# RH_Light_House.net
KiCad netlist of a schematic drawn in EasyEDA Pro
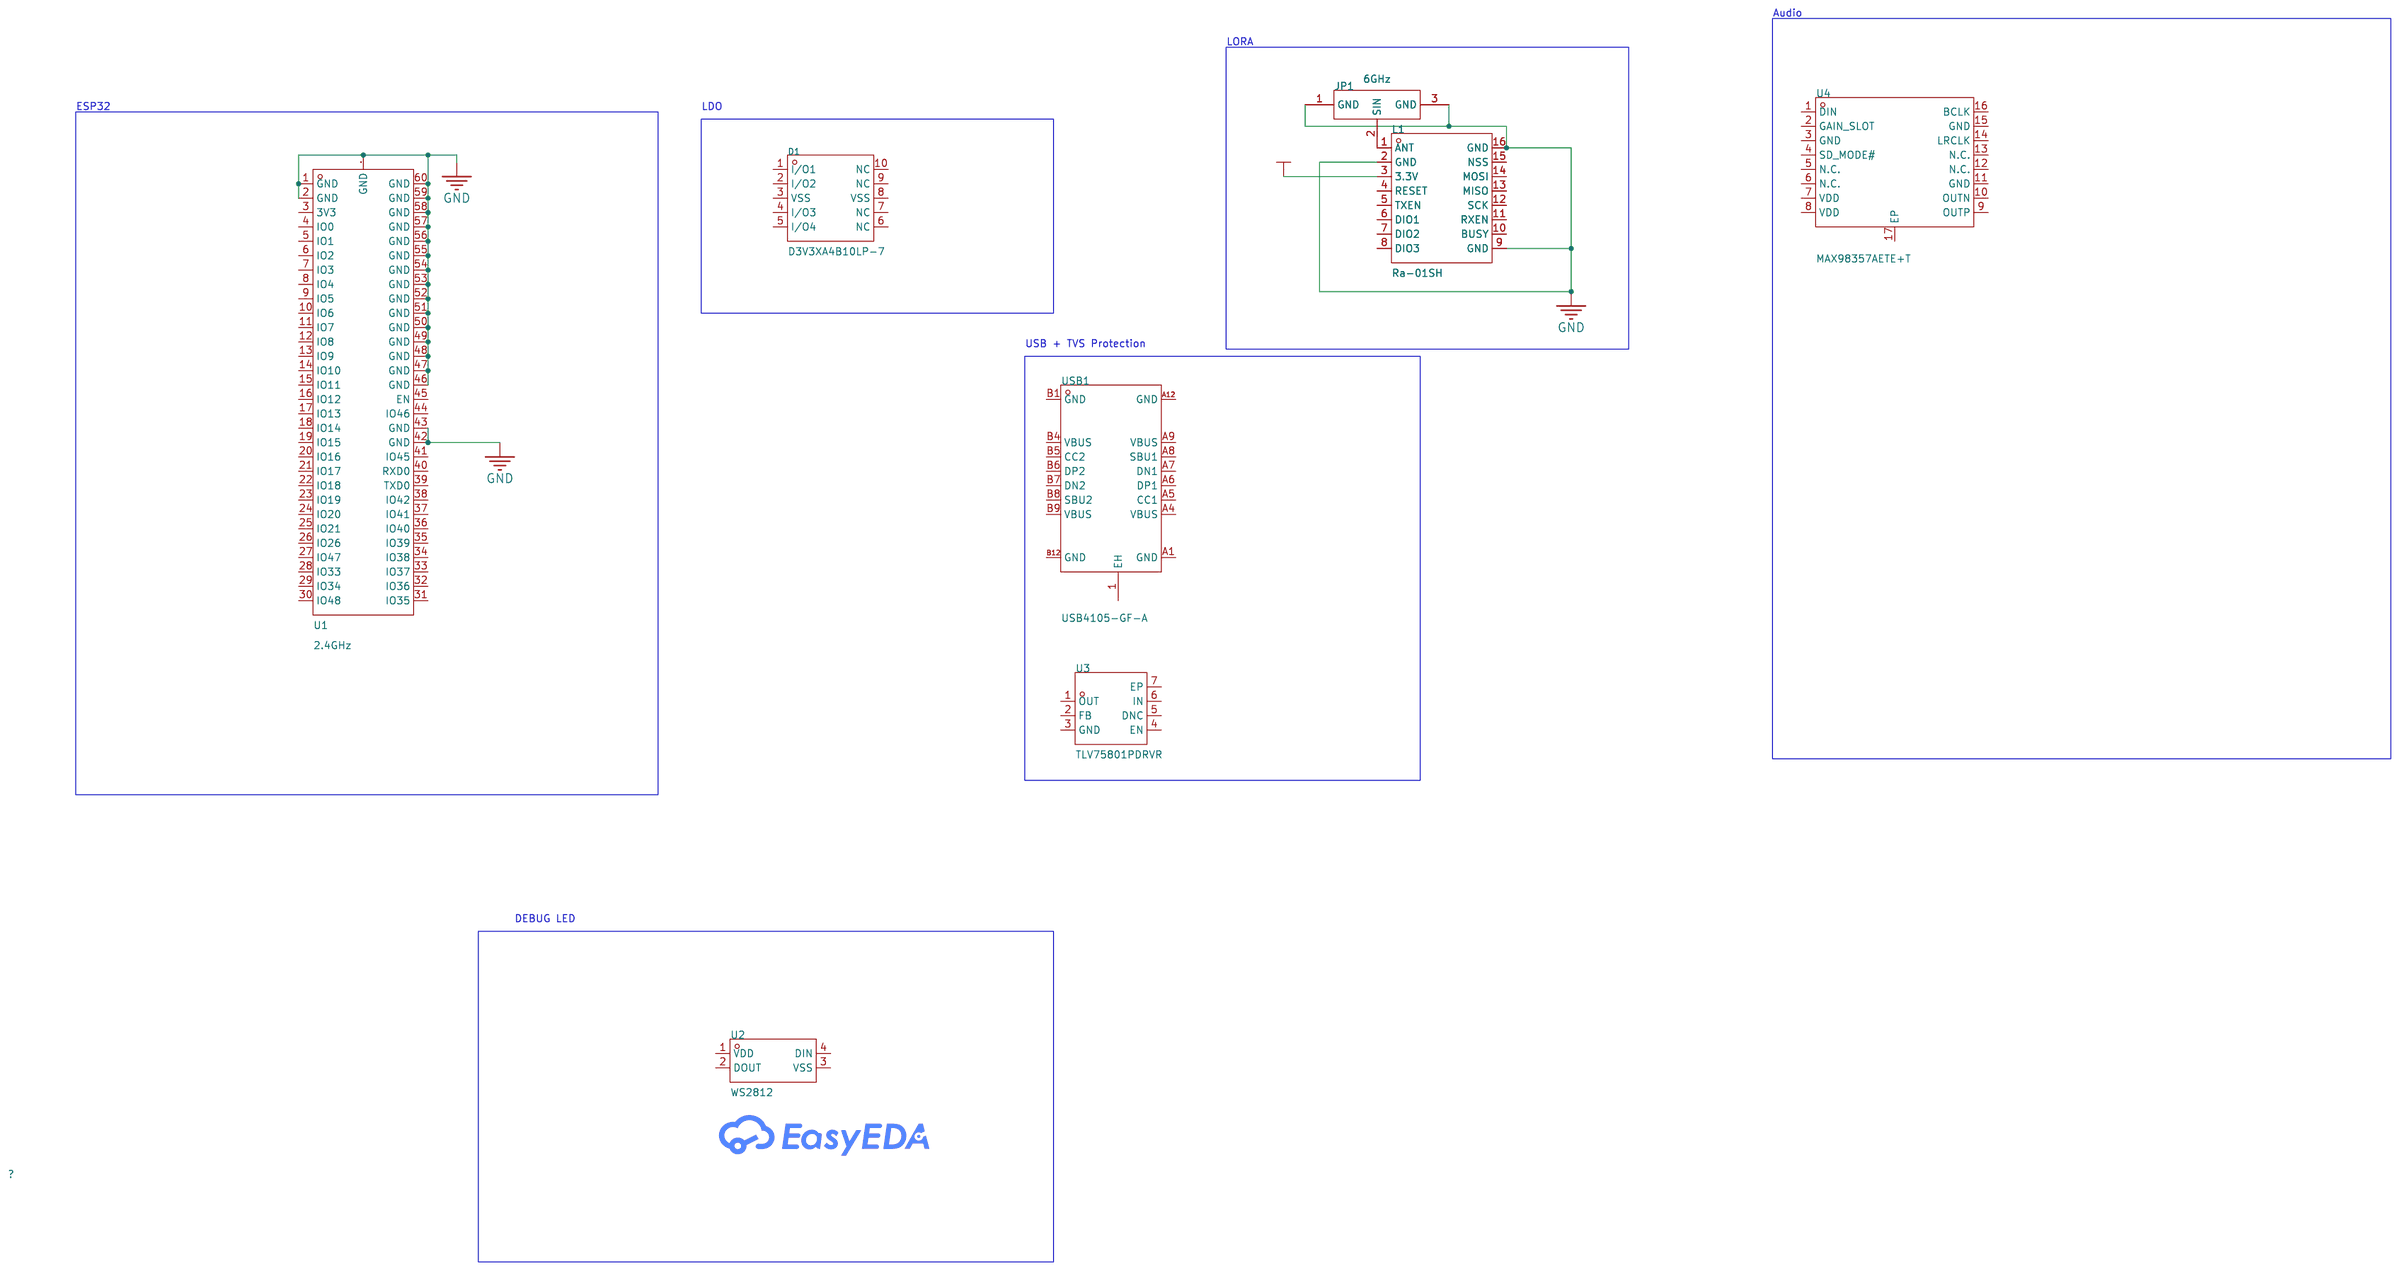
[diagram p0: schematic sheet]

(export (version "E")
  (design (tool "Eeschema 10.0.6"))
  (components
    (comp (ref "D1")
      (value "D3V3XA4B10LP-7")
      (footprint "easyedapro:U-DFN2510-10_L2.5-W1.0-P0.50-BL")
      (fields (field (name "Manufacturer") "DIODES(美台)"))
      (libsource (lib "easyedapro") (part "D3V3XA4B10LP-7"))
    )
    (comp (ref "JP1")
      (value "6GHz")
      (footprint "easyedapro:ANT-SMD_UFL-R-SMT-1-10")
      (fields (field (name "Manufacturer Part") "U.FL-R-SMT-1(10)") (field (name "Manufacturer") "HRS(广濑)"))
      (libsource (lib "easyedapro") (part "U.FL-R-SMT-1(10)"))
    )
    (comp (ref "L1")
      (value "Ra-01SH")
      (footprint "easyedapro:WIRELM-SMD_RA-01SH")
      (fields (field (name "Manufacturer") "Ai-Thinker(安信可)"))
      (libsource (lib "easyedapro") (part "RA-01SH"))
    )
    (comp (ref "U1")
      (value "2.4GHz")
      (footprint "easyedapro:BULETM-SMD_ESP32-S3-MINI-1-N8")
      (fields
        (field (name "Manufacturer Part") "ESP32-S3-MINI-1-N8")
        (field (name "Manufacturer") "ESPRESSIF(乐鑫)")
      )
      (libsource (lib "easyedapro") (part "ESP32-S3-MINI-1-N8"))
    )
    (comp (ref "U2")
      (value "WS2812")
      (footprint "easyedapro:LED-SMD_4P-L5.0-W5.0-TL-A")
      (fields (field (name "Manufacturer") "worldsemi"))
      (libsource (lib "easyedapro") (part "WS2812"))
    )
    (comp (ref "U3")
      (value "TLV75801PDRVR")
      (footprint "easyedapro:WSON-6_L2.0-W2.0-P0.65-TL-EP")
      (fields (field (name "Manufacturer") "TI(德州仪器)"))
      (libsource (lib "easyedapro") (part "TLV75801PDRVR"))
    )
    (comp (ref "U4")
      (value "MAX98357AETE+T")
      (footprint "easyedapro:TQFN-16_L3.0-W3.0-P0.50-BL-EP1.5")
      (fields (field (name "Manufacturer") "ADI(亚德诺)/MAXIM(美信)"))
      (libsource (lib "easyedapro") (part "MAX98357AETE+T"))
    )
    (comp (ref "USB1")
      (value "USB4105-GF-A")
      (footprint "easyedapro:TYPE-C-SMD_SBC-160S1A-20-S412")
      (fields (field (name "Manufacturer") "GCT"))
      (libsource (lib "easyedapro") (part "USB4105-GF-A"))
    )
  )
  (nets
    (net (code "1") (name "+3V3") (class "Default")
      (node (ref "L1") (pin "3") (pinfunction "3.3V_3") (pintype "unspecified"))
    )
    (net (code "2") (name "GND") (class "Default")
      (node (ref "JP1") (pin "1") (pinfunction "GND_1") (pintype "unspecified"))
      (node (ref "JP1") (pin "3") (pinfunction "GND_3") (pintype "unspecified"))
      (node (ref "L1") (pin "16") (pinfunction "GND_16") (pintype "unspecified"))
      (node (ref "L1") (pin "2") (pinfunction "GND_2") (pintype "unspecified"))
      (node (ref "L1") (pin "9") (pinfunction "GND_9") (pintype "unspecified"))
      (node (ref "U1") (pin "1") (pinfunction "GND_1") (pintype "unspecified"))
      (node (ref "U1") (pin "2") (pinfunction "GND_2") (pintype "unspecified"))
      (node (ref "U1") (pin "42") (pinfunction "GND_42") (pintype "unspecified"))
      (node (ref "U1") (pin "43") (pinfunction "GND_43") (pintype "unspecified"))
      (node (ref "U1") (pin "46") (pinfunction "GND_46") (pintype "unspecified"))
      (node (ref "U1") (pin "47") (pinfunction "GND_47") (pintype "unspecified"))
      (node (ref "U1") (pin "48") (pinfunction "GND_48") (pintype "unspecified"))
      (node (ref "U1") (pin "49") (pinfunction "GND_49") (pintype "unspecified"))
      (node (ref "U1") (pin "50") (pinfunction "GND_50") (pintype "unspecified"))
      (node (ref "U1") (pin "51") (pinfunction "GND_51") (pintype "unspecified"))
      (node (ref "U1") (pin "52") (pinfunction "GND_52") (pintype "unspecified"))
      (node (ref "U1") (pin "53") (pinfunction "GND_53") (pintype "unspecified"))
      (node (ref "U1") (pin "54") (pinfunction "GND_54") (pintype "unspecified"))
      (node (ref "U1") (pin "55") (pinfunction "GND_55") (pintype "unspecified"))
      (node (ref "U1") (pin "56") (pinfunction "GND_56") (pintype "unspecified"))
      (node (ref "U1") (pin "57") (pinfunction "GND_57") (pintype "unspecified"))
      (node (ref "U1") (pin "58") (pinfunction "GND_58") (pintype "unspecified"))
      (node (ref "U1") (pin "59") (pinfunction "GND_59") (pintype "unspecified"))
      (node (ref "U1") (pin "60") (pinfunction "GND_60") (pintype "unspecified"))
      (node (ref "U1") (pin "GND") (pinfunction "GND_GND") (pintype "unspecified"))
    )
    (net (code "3") (name "Net-(JP1-SIN)") (class "Default")
      (node (ref "JP1") (pin "2") (pinfunction "SIN_2") (pintype "unspecified"))
      (node (ref "L1") (pin "1") (pinfunction "ANT_1") (pintype "unspecified"))
    )
    (net (code "4") (name "unconnected-(D1-I{slash}O1-Pad1)") (class "Default")
      (node (ref "D1") (pin "1") (pinfunction "I/O1_1") (pintype "input"))
    )
    (net (code "5") (name "unconnected-(D1-I{slash}O2-Pad2)") (class "Default")
      (node (ref "D1") (pin "2") (pinfunction "I/O2_2") (pintype "input"))
    )
    (net (code "6") (name "unconnected-(D1-I{slash}O3-Pad4)") (class "Default")
      (node (ref "D1") (pin "4") (pinfunction "I/O3_4") (pintype "input"))
    )
    (net (code "7") (name "unconnected-(D1-I{slash}O4-Pad5)") (class "Default")
      (node (ref "D1") (pin "5") (pinfunction "I/O4_5") (pintype "input"))
    )
    (net (code "8") (name "unconnected-(D1-NC-Pad6)") (class "Default")
      (node (ref "D1") (pin "6") (pinfunction "NC_6") (pintype "input"))
    )
    (net (code "9") (name "unconnected-(D1-NC-Pad7)") (class "Default")
      (node (ref "D1") (pin "7") (pinfunction "NC_7") (pintype "input"))
    )
    (net (code "10") (name "unconnected-(D1-NC-Pad9)") (class "Default")
      (node (ref "D1") (pin "9") (pinfunction "NC_9") (pintype "input"))
    )
    (net (code "11") (name "unconnected-(D1-NC-Pad10)") (class "Default")
      (node (ref "D1") (pin "10") (pinfunction "NC_10") (pintype "input"))
    )
    (net (code "12") (name "unconnected-(D1-VSS-Pad3)") (class "Default")
      (node (ref "D1") (pin "3") (pinfunction "VSS_3") (pintype "input"))
    )
    (net (code "13") (name "unconnected-(D1-VSS-Pad8)") (class "Default")
      (node (ref "D1") (pin "8") (pinfunction "VSS_8") (pintype "input"))
    )
    (net (code "14") (name "unconnected-(L1-BUSY-Pad10)") (class "Default")
      (node (ref "L1") (pin "10") (pinfunction "BUSY_10") (pintype "unspecified"))
    )
    (net (code "15") (name "unconnected-(L1-DIO1-Pad6)") (class "Default")
      (node (ref "L1") (pin "6") (pinfunction "DIO1_6") (pintype "unspecified"))
    )
    (net (code "16") (name "unconnected-(L1-DIO2-Pad7)") (class "Default")
      (node (ref "L1") (pin "7") (pinfunction "DIO2_7") (pintype "unspecified"))
    )
    (net (code "17") (name "unconnected-(L1-DIO3-Pad8)") (class "Default")
      (node (ref "L1") (pin "8") (pinfunction "DIO3_8") (pintype "unspecified"))
    )
    (net (code "18") (name "unconnected-(L1-MISO-Pad13)") (class "Default")
      (node (ref "L1") (pin "13") (pinfunction "MISO_13") (pintype "unspecified"))
    )
    (net (code "19") (name "unconnected-(L1-MOSI-Pad14)") (class "Default")
      (node (ref "L1") (pin "14") (pinfunction "MOSI_14") (pintype "unspecified"))
    )
    (net (code "20") (name "unconnected-(L1-NSS-Pad15)") (class "Default")
      (node (ref "L1") (pin "15") (pinfunction "NSS_15") (pintype "unspecified"))
    )
    (net (code "21") (name "unconnected-(L1-RESET-Pad4)") (class "Default")
      (node (ref "L1") (pin "4") (pinfunction "RESET_4") (pintype "unspecified"))
    )
    (net (code "22") (name "unconnected-(L1-RXEN-Pad11)") (class "Default")
      (node (ref "L1") (pin "11") (pinfunction "RXEN_11") (pintype "unspecified"))
    )
    (net (code "23") (name "unconnected-(L1-SCK-Pad12)") (class "Default")
      (node (ref "L1") (pin "12") (pinfunction "SCK_12") (pintype "unspecified"))
    )
    (net (code "24") (name "unconnected-(L1-TXEN-Pad5)") (class "Default")
      (node (ref "L1") (pin "5") (pinfunction "TXEN_5") (pintype "unspecified"))
    )
    (net (code "25") (name "unconnected-(U1-3V3-Pad3)") (class "Default")
      (node (ref "U1") (pin "3") (pinfunction "3V3_3") (pintype "unspecified"))
    )
    (net (code "26") (name "unconnected-(U1-EN-Pad45)") (class "Default")
      (node (ref "U1") (pin "45") (pinfunction "EN_45") (pintype "unspecified"))
    )
    (net (code "27") (name "unconnected-(U1-IO0-Pad4)") (class "Default")
      (node (ref "U1") (pin "4") (pinfunction "IO0_4") (pintype "unspecified"))
    )
    (net (code "28") (name "unconnected-(U1-IO1-Pad5)") (class "Default")
      (node (ref "U1") (pin "5") (pinfunction "IO1_5") (pintype "unspecified"))
    )
    (net (code "29") (name "unconnected-(U1-IO2-Pad6)") (class "Default")
      (node (ref "U1") (pin "6") (pinfunction "IO2_6") (pintype "unspecified"))
    )
    (net (code "30") (name "unconnected-(U1-IO3-Pad7)") (class "Default")
      (node (ref "U1") (pin "7") (pinfunction "IO3_7") (pintype "unspecified"))
    )
    (net (code "31") (name "unconnected-(U1-IO4-Pad8)") (class "Default")
      (node (ref "U1") (pin "8") (pinfunction "IO4_8") (pintype "unspecified"))
    )
    (net (code "32") (name "unconnected-(U1-IO5-Pad9)") (class "Default")
      (node (ref "U1") (pin "9") (pinfunction "IO5_9") (pintype "unspecified"))
    )
    (net (code "33") (name "unconnected-(U1-IO6-Pad10)") (class "Default")
      (node (ref "U1") (pin "10") (pinfunction "IO6_10") (pintype "unspecified"))
    )
    (net (code "34") (name "unconnected-(U1-IO7-Pad11)") (class "Default")
      (node (ref "U1") (pin "11") (pinfunction "IO7_11") (pintype "unspecified"))
    )
    (net (code "35") (name "unconnected-(U1-IO8-Pad12)") (class "Default")
      (node (ref "U1") (pin "12") (pinfunction "IO8_12") (pintype "unspecified"))
    )
    (net (code "36") (name "unconnected-(U1-IO9-Pad13)") (class "Default")
      (node (ref "U1") (pin "13") (pinfunction "IO9_13") (pintype "unspecified"))
    )
    (net (code "37") (name "unconnected-(U1-IO10-Pad14)") (class "Default")
      (node (ref "U1") (pin "14") (pinfunction "IO10_14") (pintype "unspecified"))
    )
    (net (code "38") (name "unconnected-(U1-IO11-Pad15)") (class "Default")
      (node (ref "U1") (pin "15") (pinfunction "IO11_15") (pintype "unspecified"))
    )
    (net (code "39") (name "unconnected-(U1-IO12-Pad16)") (class "Default")
      (node (ref "U1") (pin "16") (pinfunction "IO12_16") (pintype "unspecified"))
    )
    (net (code "40") (name "unconnected-(U1-IO13-Pad17)") (class "Default")
      (node (ref "U1") (pin "17") (pinfunction "IO13_17") (pintype "unspecified"))
    )
    (net (code "41") (name "unconnected-(U1-IO14-Pad18)") (class "Default")
      (node (ref "U1") (pin "18") (pinfunction "IO14_18") (pintype "unspecified"))
    )
    (net (code "42") (name "unconnected-(U1-IO15-Pad19)") (class "Default")
      (node (ref "U1") (pin "19") (pinfunction "IO15_19") (pintype "unspecified"))
    )
    (net (code "43") (name "unconnected-(U1-IO16-Pad20)") (class "Default")
      (node (ref "U1") (pin "20") (pinfunction "IO16_20") (pintype "unspecified"))
    )
    (net (code "44") (name "unconnected-(U1-IO17-Pad21)") (class "Default")
      (node (ref "U1") (pin "21") (pinfunction "IO17_21") (pintype "unspecified"))
    )
    (net (code "45") (name "unconnected-(U1-IO18-Pad22)") (class "Default")
      (node (ref "U1") (pin "22") (pinfunction "IO18_22") (pintype "unspecified"))
    )
    (net (code "46") (name "unconnected-(U1-IO19-Pad23)") (class "Default")
      (node (ref "U1") (pin "23") (pinfunction "IO19_23") (pintype "unspecified"))
    )
    (net (code "47") (name "unconnected-(U1-IO20-Pad24)") (class "Default")
      (node (ref "U1") (pin "24") (pinfunction "IO20_24") (pintype "unspecified"))
    )
    (net (code "48") (name "unconnected-(U1-IO21-Pad25)") (class "Default")
      (node (ref "U1") (pin "25") (pinfunction "IO21_25") (pintype "unspecified"))
    )
    (net (code "49") (name "unconnected-(U1-IO26-Pad26)") (class "Default")
      (node (ref "U1") (pin "26") (pinfunction "IO26_26") (pintype "unspecified"))
    )
    (net (code "50") (name "unconnected-(U1-IO33-Pad28)") (class "Default")
      (node (ref "U1") (pin "28") (pinfunction "IO33_28") (pintype "unspecified"))
    )
    (net (code "51") (name "unconnected-(U1-IO34-Pad29)") (class "Default")
      (node (ref "U1") (pin "29") (pinfunction "IO34_29") (pintype "unspecified"))
    )
    (net (code "52") (name "unconnected-(U1-IO35-Pad31)") (class "Default")
      (node (ref "U1") (pin "31") (pinfunction "IO35_31") (pintype "unspecified"))
    )
    (net (code "53") (name "unconnected-(U1-IO36-Pad32)") (class "Default")
      (node (ref "U1") (pin "32") (pinfunction "IO36_32") (pintype "unspecified"))
    )
    (net (code "54") (name "unconnected-(U1-IO37-Pad33)") (class "Default")
      (node (ref "U1") (pin "33") (pinfunction "IO37_33") (pintype "unspecified"))
    )
    (net (code "55") (name "unconnected-(U1-IO38-Pad34)") (class "Default")
      (node (ref "U1") (pin "34") (pinfunction "IO38_34") (pintype "unspecified"))
    )
    (net (code "56") (name "unconnected-(U1-IO39-Pad35)") (class "Default")
      (node (ref "U1") (pin "35") (pinfunction "IO39_35") (pintype "unspecified"))
    )
    (net (code "57") (name "unconnected-(U1-IO40-Pad36)") (class "Default")
      (node (ref "U1") (pin "36") (pinfunction "IO40_36") (pintype "unspecified"))
    )
    (net (code "58") (name "unconnected-(U1-IO41-Pad37)") (class "Default")
      (node (ref "U1") (pin "37") (pinfunction "IO41_37") (pintype "unspecified"))
    )
    (net (code "59") (name "unconnected-(U1-IO42-Pad38)") (class "Default")
      (node (ref "U1") (pin "38") (pinfunction "IO42_38") (pintype "unspecified"))
    )
    (net (code "60") (name "unconnected-(U1-IO45-Pad41)") (class "Default")
      (node (ref "U1") (pin "41") (pinfunction "IO45_41") (pintype "unspecified"))
    )
    (net (code "61") (name "unconnected-(U1-IO46-Pad44)") (class "Default")
      (node (ref "U1") (pin "44") (pinfunction "IO46_44") (pintype "unspecified"))
    )
    (net (code "62") (name "unconnected-(U1-IO47-Pad27)") (class "Default")
      (node (ref "U1") (pin "27") (pinfunction "IO47_27") (pintype "unspecified"))
    )
    (net (code "63") (name "unconnected-(U1-IO48-Pad30)") (class "Default")
      (node (ref "U1") (pin "30") (pinfunction "IO48_30") (pintype "unspecified"))
    )
    (net (code "64") (name "unconnected-(U1-RXD0-Pad40)") (class "Default")
      (node (ref "U1") (pin "40") (pinfunction "RXD0_40") (pintype "unspecified"))
    )
    (net (code "65") (name "unconnected-(U1-TXD0-Pad39)") (class "Default")
      (node (ref "U1") (pin "39") (pinfunction "TXD0_39") (pintype "unspecified"))
    )
    (net (code "66") (name "unconnected-(U2-DIN-Pad4)") (class "Default")
      (node (ref "U2") (pin "4") (pinfunction "DIN_4") (pintype "unspecified"))
    )
    (net (code "67") (name "unconnected-(U2-DOUT-Pad2)") (class "Default")
      (node (ref "U2") (pin "2") (pinfunction "DOUT_2") (pintype "unspecified"))
    )
    (net (code "68") (name "unconnected-(U2-VDD-Pad1)") (class "Default")
      (node (ref "U2") (pin "1") (pinfunction "VDD_1") (pintype "unspecified"))
    )
    (net (code "69") (name "unconnected-(U2-VSS-Pad3)") (class "Default")
      (node (ref "U2") (pin "3") (pinfunction "VSS_3") (pintype "unspecified"))
    )
    (net (code "70") (name "unconnected-(U3-DNC-Pad5)") (class "Default")
      (node (ref "U3") (pin "5") (pinfunction "DNC_5") (pintype "unspecified"))
    )
    (net (code "71") (name "unconnected-(U3-EN-Pad4)") (class "Default")
      (node (ref "U3") (pin "4") (pinfunction "EN_4") (pintype "unspecified"))
    )
    (net (code "72") (name "unconnected-(U3-EP-Pad7)") (class "Default")
      (node (ref "U3") (pin "7") (pinfunction "EP_7") (pintype "unspecified"))
    )
    (net (code "73") (name "unconnected-(U3-FB-Pad2)") (class "Default")
      (node (ref "U3") (pin "2") (pinfunction "FB_2") (pintype "unspecified"))
    )
    (net (code "74") (name "unconnected-(U3-GND-Pad3)") (class "Default")
      (node (ref "U3") (pin "3") (pinfunction "GND_3") (pintype "unspecified"))
    )
    (net (code "75") (name "unconnected-(U3-IN-Pad6)") (class "Default")
      (node (ref "U3") (pin "6") (pinfunction "IN_6") (pintype "unspecified"))
    )
    (net (code "76") (name "unconnected-(U3-OUT-Pad1)") (class "Default")
      (node (ref "U3") (pin "1") (pinfunction "OUT_1") (pintype "unspecified"))
    )
    (net (code "77") (name "unconnected-(U4-BCLK-Pad16)") (class "Default")
      (node (ref "U4") (pin "16") (pinfunction "BCLK_16") (pintype "unspecified"))
    )
    (net (code "78") (name "unconnected-(U4-DIN-Pad1)") (class "Default")
      (node (ref "U4") (pin "1") (pinfunction "DIN_1") (pintype "unspecified"))
    )
    (net (code "79") (name "unconnected-(U4-EP-Pad17)") (class "Default")
      (node (ref "U4") (pin "17") (pinfunction "EP_17") (pintype "unspecified"))
    )
    (net (code "80") (name "unconnected-(U4-GAIN_SLOT-Pad2)") (class "Default")
      (node (ref "U4") (pin "2") (pinfunction "GAIN_SLOT_2") (pintype "unspecified"))
    )
    (net (code "81") (name "unconnected-(U4-GND-Pad3)") (class "Default")
      (node (ref "U4") (pin "3") (pinfunction "GND_3") (pintype "unspecified"))
    )
    (net (code "82") (name "unconnected-(U4-GND-Pad11)") (class "Default")
      (node (ref "U4") (pin "11") (pinfunction "GND_11") (pintype "unspecified"))
    )
    (net (code "83") (name "unconnected-(U4-GND-Pad15)") (class "Default")
      (node (ref "U4") (pin "15") (pinfunction "GND_15") (pintype "unspecified"))
    )
    (net (code "84") (name "unconnected-(U4-LRCLK-Pad14)") (class "Default")
      (node (ref "U4") (pin "14") (pinfunction "LRCLK_14") (pintype "unspecified"))
    )
    (net (code "85") (name "unconnected-(U4-N.C.-Pad5)") (class "Default")
      (node (ref "U4") (pin "5") (pinfunction "N.C._5") (pintype "unspecified"))
    )
    (net (code "86") (name "unconnected-(U4-N.C.-Pad6)") (class "Default")
      (node (ref "U4") (pin "6") (pinfunction "N.C._6") (pintype "unspecified"))
    )
    (net (code "87") (name "unconnected-(U4-N.C.-Pad12)") (class "Default")
      (node (ref "U4") (pin "12") (pinfunction "N.C._12") (pintype "unspecified"))
    )
    (net (code "88") (name "unconnected-(U4-N.C.-Pad13)") (class "Default")
      (node (ref "U4") (pin "13") (pinfunction "N.C._13") (pintype "unspecified"))
    )
    (net (code "89") (name "unconnected-(U4-OUTN-Pad10)") (class "Default")
      (node (ref "U4") (pin "10") (pinfunction "OUTN_10") (pintype "unspecified"))
    )
    (net (code "90") (name "unconnected-(U4-OUTP-Pad9)") (class "Default")
      (node (ref "U4") (pin "9") (pinfunction "OUTP_9") (pintype "unspecified"))
    )
    (net (code "91") (name "unconnected-(U4-SD_MODE#-Pad4)") (class "Default")
      (node (ref "U4") (pin "4") (pinfunction "SD_MODE#_4") (pintype "unspecified"))
    )
    (net (code "92") (name "unconnected-(U4-VDD-Pad7)") (class "Default")
      (node (ref "U4") (pin "7") (pinfunction "VDD_7") (pintype "unspecified"))
    )
    (net (code "93") (name "unconnected-(U4-VDD-Pad8)") (class "Default")
      (node (ref "U4") (pin "8") (pinfunction "VDD_8") (pintype "unspecified"))
    )
    (net (code "94") (name "unconnected-(USB1-CC1-PadA5)") (class "Default")
      (node (ref "USB1") (pin "A5") (pinfunction "CC1_A5") (pintype "unspecified"))
    )
    (net (code "95") (name "unconnected-(USB1-CC2-PadB5)") (class "Default")
      (node (ref "USB1") (pin "B5") (pinfunction "CC2_B5") (pintype "unspecified"))
    )
    (net (code "96") (name "unconnected-(USB1-DN1-PadA7)") (class "Default")
      (node (ref "USB1") (pin "A7") (pinfunction "DN1_A7") (pintype "unspecified"))
    )
    (net (code "97") (name "unconnected-(USB1-DN2-PadB7)") (class "Default")
      (node (ref "USB1") (pin "B7") (pinfunction "DN2_B7") (pintype "unspecified"))
    )
    (net (code "98") (name "unconnected-(USB1-DP1-PadA6)") (class "Default")
      (node (ref "USB1") (pin "A6") (pinfunction "DP1_A6") (pintype "unspecified"))
    )
    (net (code "99") (name "unconnected-(USB1-DP2-PadB6)") (class "Default")
      (node (ref "USB1") (pin "B6") (pinfunction "DP2_B6") (pintype "unspecified"))
    )
    (net (code "100") (name "unconnected-(USB1-EH-Pad1)") (class "Default")
      (node (ref "USB1") (pin "1") (pinfunction "EH_1") (pintype "unspecified"))
    )
    (net (code "101") (name "unconnected-(USB1-GND-PadA1)") (class "Default")
      (node (ref "USB1") (pin "A1") (pinfunction "GND_A1") (pintype "unspecified"))
    )
    (net (code "102") (name "unconnected-(USB1-GND-PadA12)") (class "Default")
      (node (ref "USB1") (pin "A12") (pinfunction "GND_A12") (pintype "unspecified"))
    )
    (net (code "103") (name "unconnected-(USB1-GND-PadB1)") (class "Default")
      (node (ref "USB1") (pin "B1") (pinfunction "GND_B1") (pintype "unspecified"))
    )
    (net (code "104") (name "unconnected-(USB1-GND-PadB12)") (class "Default")
      (node (ref "USB1") (pin "B12") (pinfunction "GND_B12") (pintype "unspecified"))
    )
    (net (code "105") (name "unconnected-(USB1-SBU1-PadA8)") (class "Default")
      (node (ref "USB1") (pin "A8") (pinfunction "SBU1_A8") (pintype "unspecified"))
    )
    (net (code "106") (name "unconnected-(USB1-SBU2-PadB8)") (class "Default")
      (node (ref "USB1") (pin "B8") (pinfunction "SBU2_B8") (pintype "unspecified"))
    )
    (net (code "107") (name "unconnected-(USB1-VBUS-PadA4)") (class "Default")
      (node (ref "USB1") (pin "A4") (pinfunction "VBUS_A4") (pintype "unspecified"))
    )
    (net (code "108") (name "unconnected-(USB1-VBUS-PadA9)") (class "Default")
      (node (ref "USB1") (pin "A9") (pinfunction "VBUS_A9") (pintype "unspecified"))
    )
    (net (code "109") (name "unconnected-(USB1-VBUS-PadB4)") (class "Default")
      (node (ref "USB1") (pin "B4") (pinfunction "VBUS_B4") (pintype "unspecified"))
    )
    (net (code "110") (name "unconnected-(USB1-VBUS-PadB9)") (class "Default")
      (node (ref "USB1") (pin "B9") (pinfunction "VBUS_B9") (pintype "unspecified"))
    )
  )
)
